# chandni-chhabra_week10_02-.net
KiCad netlist of a schematic drawn in EAGLE
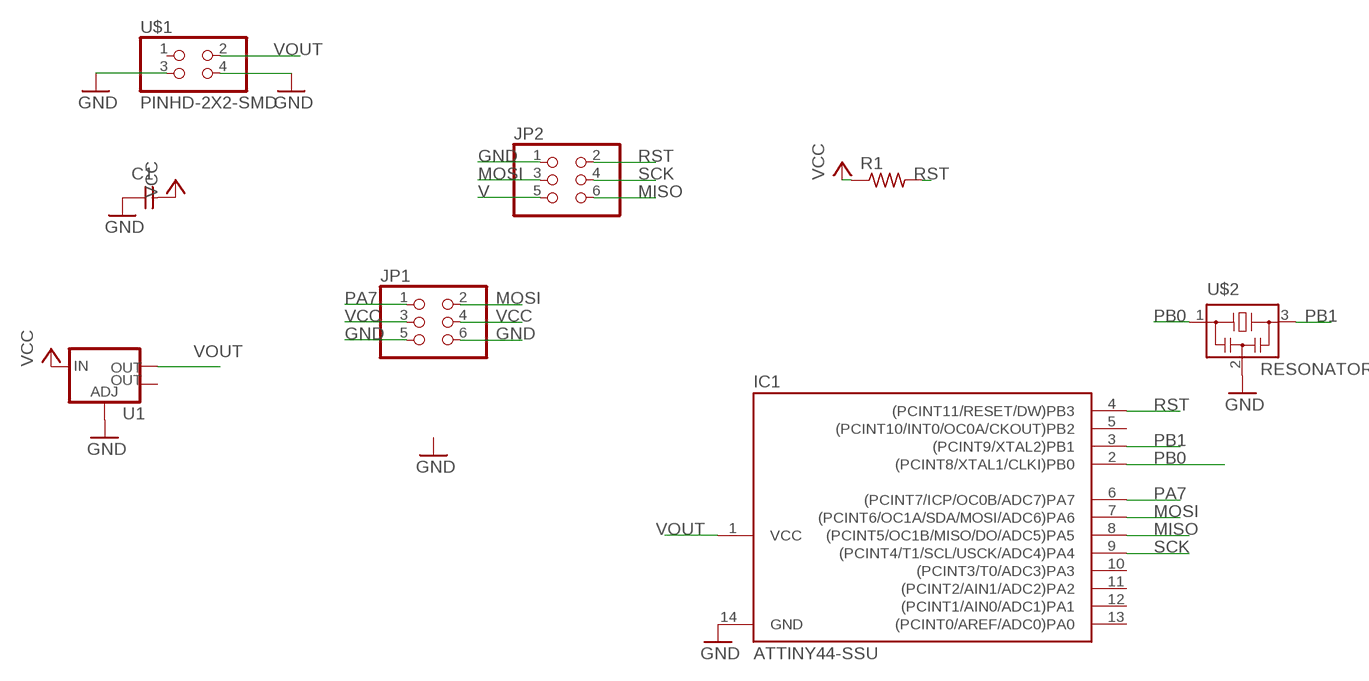
[diagram p0: schematic, sheet 1]

(export (version "E")
  (design (tool "Eeschema 10.0.6"))
  (components
    (comp (ref "C1")
      (value "CAP-UNPOLARIZEDFAB")
      (footprint "eagle-import:C1206FAB")
      (libsource (lib "eagle-import") (part "CAP-UNPOLARIZEDFAB"))
    )
    (comp (ref "IC1")
      (value "ATTINY44-SSU")
      (footprint "eagle-import:SOIC14")
      (libsource (lib "eagle-import") (part "ATTINY44-SSU"))
    )
    (comp (ref "JP1")
      (value "PINHD-2X3-SMD")
      (footprint "eagle-import:2X03SMD")
      (libsource (lib "eagle-import") (part "PINHD-2X3-SMD"))
    )
    (comp (ref "JP2")
      (value "PINHD-2X3-SMD")
      (footprint "eagle-import:2X03SMD")
      (libsource (lib "eagle-import") (part "PINHD-2X3-SMD"))
    )
    (comp (ref "R1")
      (value "RES-US1206FAB")
      (footprint "eagle-import:R1206FAB")
      (libsource (lib "eagle-import") (part "RES-US1206FAB"))
    )
    (comp (ref "U$1")
      (value "PINHD-2X2-SMD")
      (footprint "eagle-import:2X02SMD")
      (libsource (lib "eagle-import") (part "PINHD-2X2-SMD"))
    )
    (comp (ref "U$2")
      (value "RESONATOR")
      (footprint "eagle-import:EFOBM")
      (libsource (lib "eagle-import") (part "RESONATOR"))
    )
    (comp (ref "U1")
      (value "V_REG_LM1117SOT223")
      (footprint "eagle-import:SOT223")
      (libsource (lib "eagle-import") (part "V_REG_LM1117SOT223"))
    )
  )
  (nets
    (net (code "1") (name "/MISO") (class "Default")
      (node (ref "IC1") (pin "8") (pinfunction "(PCINT5/OC1B/MISO/DO/ADC5)PA5_8") (pintype "bidirectional"))
      (node (ref "JP2") (pin "6") (pinfunction "6_6") (pintype "passive"))
    )
    (net (code "2") (name "/MOSI") (class "Default")
      (node (ref "IC1") (pin "7") (pinfunction "(PCINT6/OC1A/SDA/MOSI/ADC6)PA6_7") (pintype "bidirectional"))
      (node (ref "JP1") (pin "2") (pinfunction "2_2") (pintype "passive"))
      (node (ref "JP2") (pin "3") (pinfunction "3_3") (pintype "passive"))
    )
    (net (code "3") (name "/PA7") (class "Default")
      (node (ref "IC1") (pin "6") (pinfunction "(PCINT7/ICP/OC0B/ADC7)PA7_6") (pintype "bidirectional"))
      (node (ref "JP1") (pin "1") (pinfunction "1_1") (pintype "passive"))
    )
    (net (code "4") (name "/PB0") (class "Default")
      (node (ref "IC1") (pin "2") (pinfunction "(PCINT8/XTAL1/CLKI)PB0_2") (pintype "bidirectional"))
      (node (ref "U$2") (pin "1") (pinfunction "1_1") (pintype "passive"))
    )
    (net (code "5") (name "/PB1") (class "Default")
      (node (ref "IC1") (pin "3") (pinfunction "(PCINT9/XTAL2)PB1_3") (pintype "bidirectional"))
      (node (ref "U$2") (pin "3") (pinfunction "3_3") (pintype "passive"))
    )
    (net (code "6") (name "/RST") (class "Default")
      (node (ref "IC1") (pin "4") (pinfunction "(PCINT11/RESET/DW)PB3_4") (pintype "bidirectional"))
      (node (ref "JP2") (pin "2") (pinfunction "2_2") (pintype "passive"))
      (node (ref "R1") (pin "2") (pinfunction "2_2") (pintype "passive"))
    )
    (net (code "7") (name "/SCK") (class "Default")
      (node (ref "IC1") (pin "9") (pinfunction "(PCINT4/T1/SCL/USCK/ADC4)PA4_9") (pintype "bidirectional"))
      (node (ref "JP2") (pin "4") (pinfunction "4_4") (pintype "passive"))
    )
    (net (code "8") (name "/V") (class "Default")
      (node (ref "JP2") (pin "5") (pinfunction "5_5") (pintype "passive"))
    )
    (net (code "9") (name "/VOUT") (class "Default")
      (node (ref "IC1") (pin "1") (pinfunction "VCC_1") (pintype "power_in"))
      (node (ref "U$1") (pin "2") (pinfunction "2_2") (pintype "passive"))
      (node (ref "U1") (pin "2") (pinfunction "OUT_2") (pintype "output"))
    )
    (net (code "10") (name "GND") (class "Default")
      (node (ref "C1") (pin "1") (pinfunction "1_1") (pintype "passive"))
      (node (ref "IC1") (pin "14") (pinfunction "GND_14") (pintype "power_in"))
      (node (ref "JP1") (pin "5") (pinfunction "5_5") (pintype "passive"))
      (node (ref "JP1") (pin "6") (pinfunction "6_6") (pintype "passive"))
      (node (ref "JP2") (pin "1") (pinfunction "1_1") (pintype "passive"))
      (node (ref "U$1") (pin "3") (pinfunction "3_3") (pintype "passive"))
      (node (ref "U$1") (pin "4") (pinfunction "4_4") (pintype "passive"))
      (node (ref "U$2") (pin "2") (pinfunction "2_2") (pintype "passive"))
      (node (ref "U1") (pin "1") (pinfunction "ADJ_1") (pintype "input"))
    )
    (net (code "11") (name "VCC") (class "Default")
      (node (ref "C1") (pin "2") (pinfunction "2_2") (pintype "passive"))
      (node (ref "JP1") (pin "3") (pinfunction "3_3") (pintype "passive"))
      (node (ref "JP1") (pin "4") (pinfunction "4_4") (pintype "passive"))
      (node (ref "R1") (pin "1") (pinfunction "1_1") (pintype "passive"))
      (node (ref "U1") (pin "3") (pinfunction "IN_3") (pintype "input"))
    )
    (net (code "12") (name "unconnected-(IC1-(PCINT0{slash}AREF{slash}ADC0)PA0-Pad13)") (class "Default")
      (node (ref "IC1") (pin "13") (pinfunction "(PCINT0/AREF/ADC0)PA0_13") (pintype "bidirectional"))
    )
    (net (code "13") (name "unconnected-(IC1-(PCINT1{slash}AIN0{slash}ADC1)PA1-Pad12)") (class "Default")
      (node (ref "IC1") (pin "12") (pinfunction "(PCINT1/AIN0/ADC1)PA1_12") (pintype "bidirectional"))
    )
    (net (code "14") (name "unconnected-(IC1-(PCINT2{slash}AIN1{slash}ADC2)PA2-Pad11)") (class "Default")
      (node (ref "IC1") (pin "11") (pinfunction "(PCINT2/AIN1/ADC2)PA2_11") (pintype "bidirectional"))
    )
    (net (code "15") (name "unconnected-(IC1-(PCINT3{slash}T0{slash}ADC3)PA3-Pad10)") (class "Default")
      (node (ref "IC1") (pin "10") (pinfunction "(PCINT3/T0/ADC3)PA3_10") (pintype "bidirectional"))
    )
    (net (code "16") (name "unconnected-(IC1-(PCINT10{slash}INT0{slash}OC0A{slash}CKOUT)PB2-Pad5)") (class "Default")
      (node (ref "IC1") (pin "5") (pinfunction "(PCINT10/INT0/OC0A/CKOUT)PB2_5") (pintype "bidirectional"))
    )
    (net (code "17") (name "unconnected-(U$1-Pad1)") (class "Default")
      (node (ref "U$1") (pin "1") (pinfunction "1_1") (pintype "passive"))
    )
    (net (code "18") (name "unconnected-(U1-OUT-Pad4)") (class "Default")
      (node (ref "U1") (pin "4") (pinfunction "OUT_4") (pintype "output"))
    )
  )
)
